# 02_MCU_ANALOG.net
KiCad netlist of a schematic drawn in Altium Designer
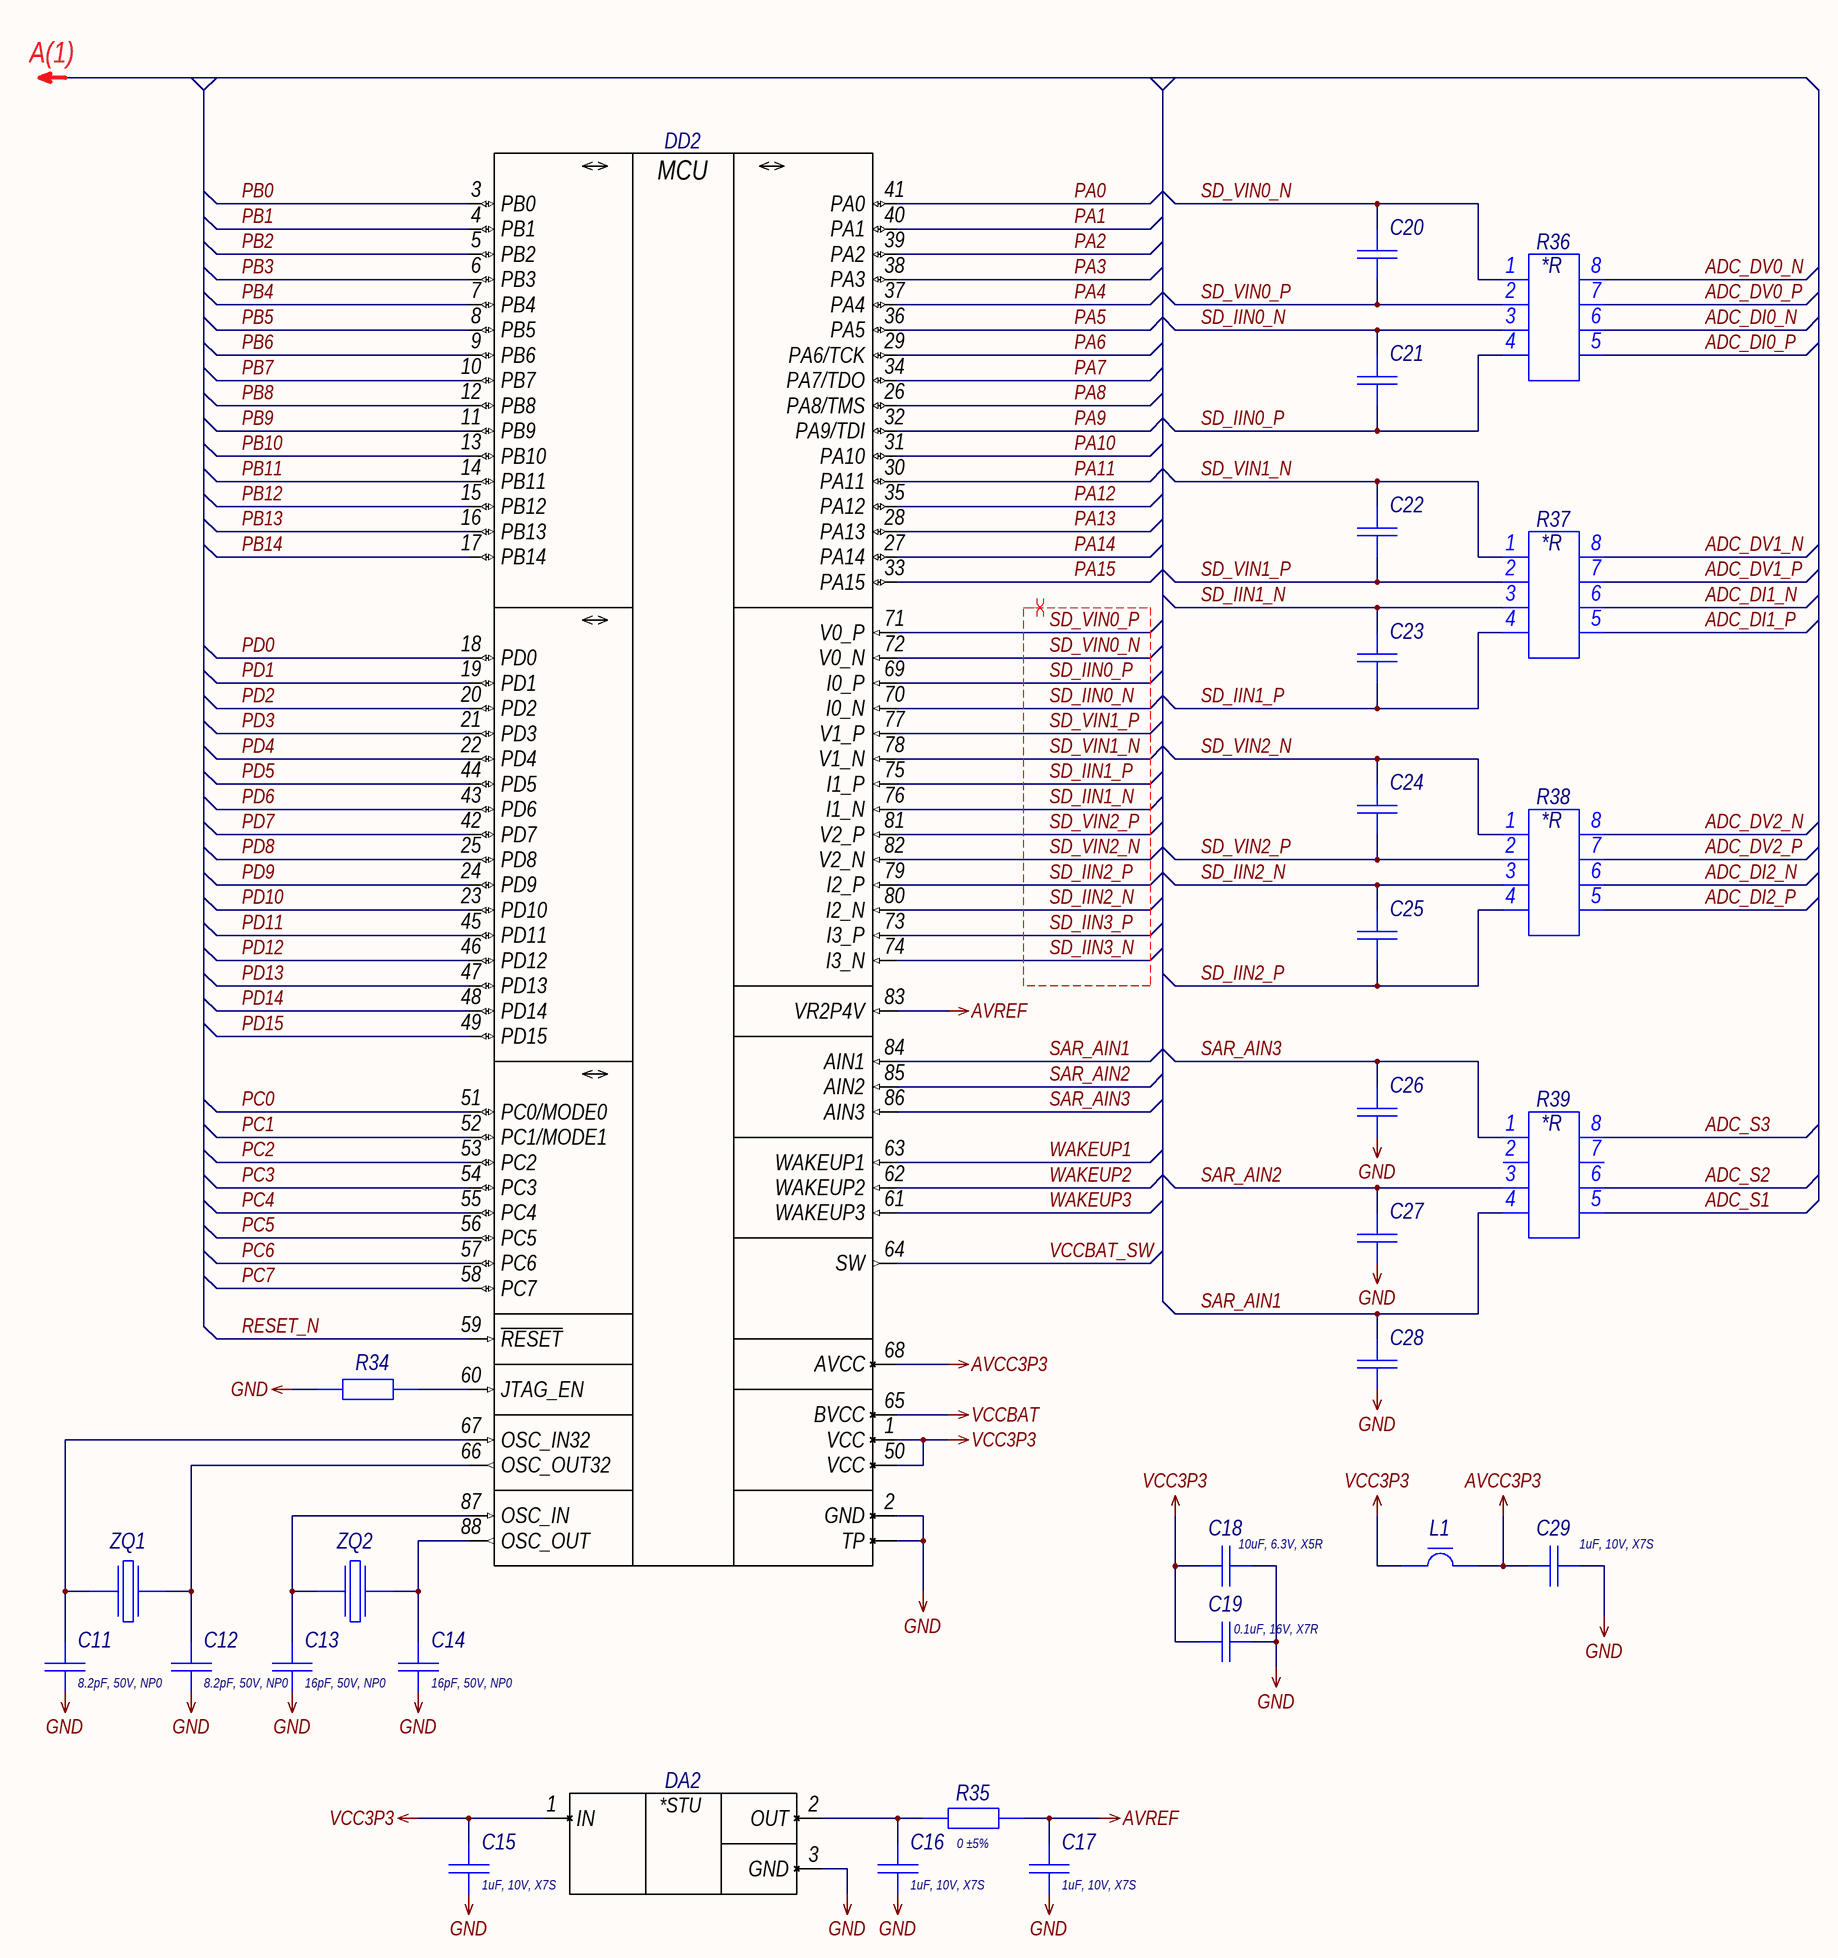
[diagram p0: 02_MCU_ANALOG.SchDoc]

(export (version "E")
  (design (tool "Eeschema 10.0.6"))
  (components
    (comp (ref "C11")
      (value "Capacitor")
      (footprint "C0402_100X050H050_H")
      (fields
        (field (name "SCHEMATIC VALUE") "8.2pF, 50V, NP0")
        (field (name "PART NUMBER") "GCM1555C1H8R2CA16D")
        (field (name "VOLTAGE") "50V")
        (field (name "TOLERANCE") "±0.25pF")
        (field (name "PUBLISHER") "Andrew Danich")
      )
      (libsource (lib "ADLib") (part "Capacitor"))
    )
    (comp (ref "C12")
      (value "Capacitor")
      (footprint "C0402_100X050H050_H")
      (fields
        (field (name "SCHEMATIC VALUE") "8.2pF, 50V, NP0")
        (field (name "PART NUMBER") "GCM1555C1H8R2CA16D")
        (field (name "VOLTAGE") "50V")
        (field (name "TOLERANCE") "±0.25pF")
        (field (name "PUBLISHER") "Andrew Danich")
      )
      (libsource (lib "ADLib") (part "Capacitor"))
    )
    (comp (ref "C13")
      (value "Capacitor")
      (footprint "C0402_100X050H050_H")
      (fields
        (field (name "SCHEMATIC VALUE") "16pF, 50V, NP0")
        (field (name "PART NUMBER") "GRM1555C1H160JA01D")
        (field (name "VOLTAGE") "50V")
        (field (name "TOLERANCE") "±5%")
        (field (name "PUBLISHER") "Andrew Danich")
      )
      (libsource (lib "ADLib") (part "Capacitor"))
    )
    (comp (ref "C14")
      (value "Capacitor")
      (footprint "C0402_100X050H050_H")
      (fields
        (field (name "SCHEMATIC VALUE") "16pF, 50V, NP0")
        (field (name "PART NUMBER") "GRM1555C1H160JA01D")
        (field (name "VOLTAGE") "50V")
        (field (name "TOLERANCE") "±5%")
        (field (name "PUBLISHER") "Andrew Danich")
      )
      (libsource (lib "ADLib") (part "Capacitor"))
    )
    (comp (ref "C15")
      (value "Capacitor")
      (footprint "C0402_100X050H050_H")
      (fields
        (field (name "SCHEMATIC VALUE") "1uF, 10V, X7S")
        (field (name "PART NUMBER") "GRM155C71A105KE11D")
        (field (name "VOLTAGE") "10V")
        (field (name "TOLERANCE") "±10%")
        (field (name "PUBLISHER") "Andrew Danich")
      )
      (libsource (lib "ADLib") (part "Capacitor"))
    )
    (comp (ref "C16")
      (value "Capacitor")
      (footprint "C0402_100X050H050_H")
      (fields
        (field (name "SCHEMATIC VALUE") "1uF, 10V, X7S")
        (field (name "PART NUMBER") "GRM155C71A105KE11D")
        (field (name "VOLTAGE") "10V")
        (field (name "TOLERANCE") "±10%")
        (field (name "PUBLISHER") "Andrew Danich")
      )
      (libsource (lib "ADLib") (part "Capacitor"))
    )
    (comp (ref "C17")
      (value "Capacitor")
      (footprint "C0402_100X050H050_H")
      (fields
        (field (name "SCHEMATIC VALUE") "1uF, 10V, X7S")
        (field (name "PART NUMBER") "GRM155C71A105KE11D")
        (field (name "VOLTAGE") "10V")
        (field (name "TOLERANCE") "±10%")
        (field (name "PUBLISHER") "Andrew Danich")
      )
      (libsource (lib "ADLib") (part "Capacitor"))
    )
    (comp (ref "C18")
      (value "Capacitor")
      (footprint "C0402_100X050H050_H")
      (fields
        (field (name "SCHEMATIC VALUE") "10uF, 6.3V, X5R")
        (field (name "PART NUMBER") "GRM155R60J106ME15D")
        (field (name "VOLTAGE") "6.3V")
        (field (name "TOLERANCE") "±20%")
        (field (name "PUBLISHER") "Andrew Danich")
      )
      (libsource (lib "ADLib") (part "Capacitor"))
    )
    (comp (ref "C19")
      (value "Capacitor")
      (footprint "C0402_100X050H050_H")
      (fields
        (field (name "SCHEMATIC VALUE") "0.1uF, 16V, X7R")
        (field (name "PART NUMBER") "GCM155R71C104KA55D")
        (field (name "VOLTAGE") "16V")
        (field (name "TOLERANCE") "±10%")
        (field (name "PUBLISHER") "Andrew Danich")
      )
      (libsource (lib "ADLib") (part "Capacitor"))
    )
    (comp (ref "C20")
      (value "Capacitor")
      (footprint "C0201_060X030H030_H")
      (fields
        (field (name "PART NUMBER") "GRM033R71A472KA01D")
        (field (name "VOLTAGE") "10V")
        (field (name "TOLERANCE") "±10%")
        (field (name "PUBLISHER") "Andrew Danich")
      )
      (libsource (lib "ADLib") (part "Capacitor"))
    )
    (comp (ref "C21")
      (value "Capacitor")
      (footprint "C0201_060X030H030_H")
      (fields
        (field (name "PART NUMBER") "GRM033R71A472KA01D")
        (field (name "VOLTAGE") "10V")
        (field (name "TOLERANCE") "±10%")
        (field (name "PUBLISHER") "Andrew Danich")
      )
      (libsource (lib "ADLib") (part "Capacitor"))
    )
    (comp (ref "C22")
      (value "Capacitor")
      (footprint "C0201_060X030H030_H")
      (fields
        (field (name "PART NUMBER") "GRM033R71A472KA01D")
        (field (name "VOLTAGE") "10V")
        (field (name "TOLERANCE") "±10%")
        (field (name "PUBLISHER") "Andrew Danich")
      )
      (libsource (lib "ADLib") (part "Capacitor"))
    )
    (comp (ref "C23")
      (value "Capacitor")
      (footprint "C0201_060X030H030_H")
      (fields
        (field (name "PART NUMBER") "GRM033R71A472KA01D")
        (field (name "VOLTAGE") "10V")
        (field (name "TOLERANCE") "±10%")
        (field (name "PUBLISHER") "Andrew Danich")
      )
      (libsource (lib "ADLib") (part "Capacitor"))
    )
    (comp (ref "C24")
      (value "Capacitor")
      (footprint "C0201_060X030H030_H")
      (fields
        (field (name "PART NUMBER") "GRM033R71A472KA01D")
        (field (name "VOLTAGE") "10V")
        (field (name "TOLERANCE") "±10%")
        (field (name "PUBLISHER") "Andrew Danich")
      )
      (libsource (lib "ADLib") (part "Capacitor"))
    )
    (comp (ref "C25")
      (value "Capacitor")
      (footprint "C0201_060X030H030_H")
      (fields
        (field (name "PART NUMBER") "GRM033R71A472KA01D")
        (field (name "VOLTAGE") "10V")
        (field (name "TOLERANCE") "±10%")
        (field (name "PUBLISHER") "Andrew Danich")
      )
      (libsource (lib "ADLib") (part "Capacitor"))
    )
    (comp (ref "C26")
      (value "Capacitor")
      (footprint "C0201_060X030H030_H")
      (fields
        (field (name "PART NUMBER") "GRM033R71A472KA01D")
        (field (name "VOLTAGE") "10V")
        (field (name "TOLERANCE") "±10%")
        (field (name "PUBLISHER") "Andrew Danich")
      )
      (libsource (lib "ADLib") (part "Capacitor"))
    )
    (comp (ref "C27")
      (value "Capacitor")
      (footprint "C0201_060X030H030_H")
      (fields
        (field (name "PART NUMBER") "GRM033R71A472KA01D")
        (field (name "VOLTAGE") "10V")
        (field (name "TOLERANCE") "±10%")
        (field (name "PUBLISHER") "Andrew Danich")
      )
      (libsource (lib "ADLib") (part "Capacitor"))
    )
    (comp (ref "C28")
      (value "Capacitor")
      (footprint "C0201_060X030H030_H")
      (fields
        (field (name "PART NUMBER") "GRM033R71A472KA01D")
        (field (name "VOLTAGE") "10V")
        (field (name "TOLERANCE") "±10%")
        (field (name "PUBLISHER") "Andrew Danich")
      )
      (libsource (lib "ADLib") (part "Capacitor"))
    )
    (comp (ref "C29")
      (value "Capacitor")
      (footprint "C0402_100X050H050_H")
      (fields
        (field (name "SCHEMATIC VALUE") "1uF, 10V, X7S")
        (field (name "PART NUMBER") "GRM155C71A105KE11D")
        (field (name "VOLTAGE") "10V")
        (field (name "TOLERANCE") "±10%")
        (field (name "PUBLISHER") "Andrew Danich")
      )
      (libsource (lib "ADLib") (part "Capacitor"))
    )
    (comp (ref "DA2")
      (value "REF33xxAIDBZx-Series")
      (footprint "SOT-23_190P290X160X145_N")
      (fields
        (field (name "PART NUMBER") "REF3325AIDBZR")
        (field (name "MANUFACTURER") "Texas Instruments")
        (field (name "PUBLISHER") "Andrew Danich")
      )
      (libsource (lib "ADLib") (part "REF33xxAIDBZx-Series"))
    )
    (comp (ref "DD2")
      (value "1986ВК025-Series")
      (footprint "QFN-88_040P1000X1000X080_N")
      (fields
        (field (name "PART NUMBER") "К1986ВК025")
        (field (name "MANUFACTURER") "Миландр")
        (field (name "PUBLISHER") "Andrew Danich")
      )
      (libsource (lib "ADLib_RUS") (part "1986ВК025-Series"))
    )
    (comp (ref "L1")
      (value "FerriteBead")
      (footprint "L0402_100X050H050_H")
      (fields
        (field (name "PART NUMBER") "BLM15HD102SN1D")
        (field (name "TOLERANCE") "±25%")
        (field (name "MANUFACTURER") "Murata")
        (field (name "PUBLISHER") "Andrew Danich")
      )
      (libsource (lib "ADLib") (part "FerriteBead"))
    )
    (comp (ref "R34")
      (value "Resistor")
      (footprint "R0402_100X050H035_H")
      (fields
        (field (name "PART NUMBER") "RC0402JR-070RL")
        (field (name "TOLERANCE") "±5%")
        (field (name "MANUFACTURER") "Yageo")
        (field (name "PUBLISHER") "Andrew Danich")
      )
      (libsource (lib "ADLib") (part "Resistor"))
    )
    (comp (ref "R35")
      (value "Resistor")
      (footprint "R0402_100X050H035_H")
      (fields
        (field (name "PART NUMBER") "RC0402JR-070RL")
        (field (name "TOLERANCE") "±5%")
        (field (name "MANUFACTURER") "Yageo")
        (field (name "SCHEMATIC VALUE") "0 ±5%")
        (field (name "PUBLISHER") "Andrew Danich")
      )
      (libsource (lib "ADLib") (part "Resistor"))
    )
    (comp (ref "R36")
      (value "Resistor-4")
      (footprint "CAY10-x4")
      (fields
        (field (name "PART NUMBER") "CAY10-101J4LF")
        (field (name "TOLERANCE") "±5%")
        (field (name "MANUFACTURER") "Bourns")
        (field (name "PUBLISHER") "Andrew Danich")
      )
      (libsource (lib "ADLib") (part "Resistor-4"))
    )
    (comp (ref "R37")
      (value "Resistor-4")
      (footprint "CAY10-x4")
      (fields
        (field (name "PART NUMBER") "CAY10-101J4LF")
        (field (name "TOLERANCE") "±5%")
        (field (name "MANUFACTURER") "Bourns")
        (field (name "PUBLISHER") "Andrew Danich")
      )
      (libsource (lib "ADLib") (part "Resistor-4"))
    )
    (comp (ref "R38")
      (value "Resistor-4")
      (footprint "CAY10-x4")
      (fields
        (field (name "PART NUMBER") "CAY10-101J4LF")
        (field (name "TOLERANCE") "±5%")
        (field (name "MANUFACTURER") "Bourns")
        (field (name "PUBLISHER") "Andrew Danich")
      )
      (libsource (lib "ADLib") (part "Resistor-4"))
    )
    (comp (ref "R39")
      (value "Resistor-4")
      (footprint "CAY10-x4")
      (fields
        (field (name "PART NUMBER") "CAY10-101J4LF")
        (field (name "TOLERANCE") "±5%")
        (field (name "MANUFACTURER") "Bourns")
        (field (name "PUBLISHER") "Andrew Danich")
      )
      (libsource (lib "ADLib") (part "Resistor-4"))
    )
    (comp (ref "ZQ1")
      (value "Crystal")
      (footprint "SX-3215")
      (fields (field (name "PART NUMBER") "SX-3215 32.768KHz") (field (name "PUBLISHER") "Andrew Danich"))
      (libsource (lib "ADLib") (part "Crystal"))
    )
    (comp (ref "ZQ2")
      (value "Crystal-1_3p")
      (footprint "SMD 3.2x2.5mm")
      (fields
        (field (name "PART NUMBER") "12.88602_KX-7-16.0MHz")
        (field (name "MANUFACTURER") "GEYER ELECTRONIC")
        (field (name "PUBLISHER") "Andrew Danich")
      )
      (libsource (lib "ADLib") (part "Crystal-1_3p"))
    )
  )
  (nets
    (net (code "1") (name "/ADC_DI0_N") (class "Default") (node (ref "R36") (pin "6") (pintype "passive")))
    (net (code "2") (name "/ADC_DI0_P") (class "Default") (node (ref "R36") (pin "5") (pintype "passive")))
    (net (code "3") (name "/ADC_DI1_N") (class "Default") (node (ref "R37") (pin "6") (pintype "passive")))
    (net (code "4") (name "/ADC_DI1_P") (class "Default") (node (ref "R37") (pin "5") (pintype "passive")))
    (net (code "5") (name "/ADC_DI2_N") (class "Default") (node (ref "R38") (pin "6") (pintype "passive")))
    (net (code "6") (name "/ADC_DI2_P") (class "Default") (node (ref "R38") (pin "5") (pintype "passive")))
    (net (code "7") (name "/ADC_DV0_N") (class "Default") (node (ref "R36") (pin "8") (pintype "passive")))
    (net (code "8") (name "/ADC_DV0_P") (class "Default") (node (ref "R36") (pin "7") (pintype "passive")))
    (net (code "9") (name "/ADC_DV1_N") (class "Default") (node (ref "R37") (pin "8") (pintype "passive")))
    (net (code "10") (name "/ADC_DV1_P") (class "Default") (node (ref "R37") (pin "7") (pintype "passive")))
    (net (code "11") (name "/ADC_DV2_N") (class "Default") (node (ref "R38") (pin "8") (pintype "passive")))
    (net (code "12") (name "/ADC_DV2_P") (class "Default") (node (ref "R38") (pin "7") (pintype "passive")))
    (net (code "13") (name "/ADC_S1") (class "Default") (node (ref "R39") (pin "5") (pintype "passive")))
    (net (code "14") (name "/ADC_S2") (class "Default") (node (ref "R39") (pin "6") (pintype "passive")))
    (net (code "15") (name "/ADC_S3") (class "Default") (node (ref "R39") (pin "8") (pintype "passive")))
    (net (code "16") (name "/PA0") (class "Default")
      (node (ref "DD2") (pin "41") (pinfunction "PA0_41") (pintype "bidirectional"))
    )
    (net (code "17") (name "/PA1") (class "Default")
      (node (ref "DD2") (pin "40") (pinfunction "PA1_40") (pintype "bidirectional"))
    )
    (net (code "18") (name "/PA2") (class "Default")
      (node (ref "DD2") (pin "39") (pinfunction "PA2_39") (pintype "bidirectional"))
    )
    (net (code "19") (name "/PA3") (class "Default")
      (node (ref "DD2") (pin "38") (pinfunction "PA3_38") (pintype "bidirectional"))
    )
    (net (code "20") (name "/PA4") (class "Default")
      (node (ref "DD2") (pin "37") (pinfunction "PA4_37") (pintype "bidirectional"))
    )
    (net (code "21") (name "/PA5") (class "Default")
      (node (ref "DD2") (pin "36") (pinfunction "PA5_36") (pintype "bidirectional"))
    )
    (net (code "22") (name "/PA6") (class "Default")
      (node (ref "DD2") (pin "29") (pinfunction "PA6/TCK_29") (pintype "bidirectional"))
    )
    (net (code "23") (name "/PA7") (class "Default")
      (node (ref "DD2") (pin "34") (pinfunction "PA7/TDO_34") (pintype "bidirectional"))
    )
    (net (code "24") (name "/PA8") (class "Default")
      (node (ref "DD2") (pin "26") (pinfunction "PA8/TMS_26") (pintype "bidirectional"))
    )
    (net (code "25") (name "/PA9") (class "Default")
      (node (ref "DD2") (pin "32") (pinfunction "PA9/TDI_32") (pintype "bidirectional"))
    )
    (net (code "26") (name "/PA10") (class "Default")
      (node (ref "DD2") (pin "31") (pinfunction "PA10_31") (pintype "bidirectional"))
    )
    (net (code "27") (name "/PA11") (class "Default")
      (node (ref "DD2") (pin "30") (pinfunction "PA11_30") (pintype "bidirectional"))
    )
    (net (code "28") (name "/PA12") (class "Default")
      (node (ref "DD2") (pin "35") (pinfunction "PA12_35") (pintype "bidirectional"))
    )
    (net (code "29") (name "/PA13") (class "Default")
      (node (ref "DD2") (pin "28") (pinfunction "PA13_28") (pintype "bidirectional"))
    )
    (net (code "30") (name "/PA14") (class "Default")
      (node (ref "DD2") (pin "27") (pinfunction "PA14_27") (pintype "bidirectional"))
    )
    (net (code "31") (name "/PA15") (class "Default")
      (node (ref "DD2") (pin "33") (pinfunction "PA15_33") (pintype "bidirectional"))
    )
    (net (code "32") (name "/PB0") (class "Default")
      (node (ref "DD2") (pin "3") (pinfunction "PB0_3") (pintype "bidirectional"))
    )
    (net (code "33") (name "/PB1") (class "Default")
      (node (ref "DD2") (pin "4") (pinfunction "PB1_4") (pintype "bidirectional"))
    )
    (net (code "34") (name "/PB2") (class "Default")
      (node (ref "DD2") (pin "5") (pinfunction "PB2_5") (pintype "bidirectional"))
    )
    (net (code "35") (name "/PB3") (class "Default")
      (node (ref "DD2") (pin "6") (pinfunction "PB3_6") (pintype "bidirectional"))
    )
    (net (code "36") (name "/PB4") (class "Default")
      (node (ref "DD2") (pin "7") (pinfunction "PB4_7") (pintype "bidirectional"))
    )
    (net (code "37") (name "/PB5") (class "Default")
      (node (ref "DD2") (pin "8") (pinfunction "PB5_8") (pintype "bidirectional"))
    )
    (net (code "38") (name "/PB6") (class "Default")
      (node (ref "DD2") (pin "9") (pinfunction "PB6_9") (pintype "bidirectional"))
    )
    (net (code "39") (name "/PB7") (class "Default")
      (node (ref "DD2") (pin "10") (pinfunction "PB7_10") (pintype "bidirectional"))
    )
    (net (code "40") (name "/PB8") (class "Default")
      (node (ref "DD2") (pin "12") (pinfunction "PB8_12") (pintype "bidirectional"))
    )
    (net (code "41") (name "/PB9") (class "Default")
      (node (ref "DD2") (pin "11") (pinfunction "PB9_11") (pintype "bidirectional"))
    )
    (net (code "42") (name "/PB10") (class "Default")
      (node (ref "DD2") (pin "13") (pinfunction "PB10_13") (pintype "bidirectional"))
    )
    (net (code "43") (name "/PB11") (class "Default")
      (node (ref "DD2") (pin "14") (pinfunction "PB11_14") (pintype "bidirectional"))
    )
    (net (code "44") (name "/PB12") (class "Default")
      (node (ref "DD2") (pin "15") (pinfunction "PB12_15") (pintype "bidirectional"))
    )
    (net (code "45") (name "/PB13") (class "Default")
      (node (ref "DD2") (pin "16") (pinfunction "PB13_16") (pintype "bidirectional"))
    )
    (net (code "46") (name "/PB14") (class "Default")
      (node (ref "DD2") (pin "17") (pinfunction "PB14_17") (pintype "bidirectional"))
    )
    (net (code "47") (name "/PC0") (class "Default")
      (node (ref "DD2") (pin "51") (pinfunction "PC0/MODE0_51") (pintype "bidirectional"))
    )
    (net (code "48") (name "/PC1") (class "Default")
      (node (ref "DD2") (pin "52") (pinfunction "PC1/MODE1_52") (pintype "bidirectional"))
    )
    (net (code "49") (name "/PC2") (class "Default")
      (node (ref "DD2") (pin "53") (pinfunction "PC2_53") (pintype "bidirectional"))
    )
    (net (code "50") (name "/PC3") (class "Default")
      (node (ref "DD2") (pin "54") (pinfunction "PC3_54") (pintype "bidirectional"))
    )
    (net (code "51") (name "/PC4") (class "Default")
      (node (ref "DD2") (pin "55") (pinfunction "PC4_55") (pintype "bidirectional"))
    )
    (net (code "52") (name "/PC5") (class "Default")
      (node (ref "DD2") (pin "56") (pinfunction "PC5_56") (pintype "bidirectional"))
    )
    (net (code "53") (name "/PC6") (class "Default")
      (node (ref "DD2") (pin "57") (pinfunction "PC6_57") (pintype "bidirectional"))
    )
    (net (code "54") (name "/PC7") (class "Default")
      (node (ref "DD2") (pin "58") (pinfunction "PC7_58") (pintype "bidirectional"))
    )
    (net (code "55") (name "/PD0") (class "Default")
      (node (ref "DD2") (pin "18") (pinfunction "PD0_18") (pintype "bidirectional"))
    )
    (net (code "56") (name "/PD1") (class "Default")
      (node (ref "DD2") (pin "19") (pinfunction "PD1_19") (pintype "bidirectional"))
    )
    (net (code "57") (name "/PD2") (class "Default")
      (node (ref "DD2") (pin "20") (pinfunction "PD2_20") (pintype "bidirectional"))
    )
    (net (code "58") (name "/PD3") (class "Default")
      (node (ref "DD2") (pin "21") (pinfunction "PD3_21") (pintype "bidirectional"))
    )
    (net (code "59") (name "/PD4") (class "Default")
      (node (ref "DD2") (pin "22") (pinfunction "PD4_22") (pintype "bidirectional"))
    )
    (net (code "60") (name "/PD5") (class "Default")
      (node (ref "DD2") (pin "44") (pinfunction "PD5_44") (pintype "bidirectional"))
    )
    (net (code "61") (name "/PD6") (class "Default")
      (node (ref "DD2") (pin "43") (pinfunction "PD6_43") (pintype "bidirectional"))
    )
    (net (code "62") (name "/PD7") (class "Default")
      (node (ref "DD2") (pin "42") (pinfunction "PD7_42") (pintype "bidirectional"))
    )
    (net (code "63") (name "/PD8") (class "Default")
      (node (ref "DD2") (pin "25") (pinfunction "PD8_25") (pintype "bidirectional"))
    )
    (net (code "64") (name "/PD9") (class "Default")
      (node (ref "DD2") (pin "24") (pinfunction "PD9_24") (pintype "bidirectional"))
    )
    (net (code "65") (name "/PD10") (class "Default")
      (node (ref "DD2") (pin "23") (pinfunction "PD10_23") (pintype "bidirectional"))
    )
    (net (code "66") (name "/PD11") (class "Default")
      (node (ref "DD2") (pin "45") (pinfunction "PD11_45") (pintype "bidirectional"))
    )
    (net (code "67") (name "/PD12") (class "Default")
      (node (ref "DD2") (pin "46") (pinfunction "PD12_46") (pintype "bidirectional"))
    )
    (net (code "68") (name "/PD13") (class "Default")
      (node (ref "DD2") (pin "47") (pinfunction "PD13_47") (pintype "bidirectional"))
    )
    (net (code "69") (name "/PD14") (class "Default")
      (node (ref "DD2") (pin "48") (pinfunction "PD14_48") (pintype "bidirectional"))
    )
    (net (code "70") (name "/PD15") (class "Default")
      (node (ref "DD2") (pin "49") (pinfunction "PD15_49") (pintype "bidirectional"))
    )
    (net (code "71") (name "/RESET_N") (class "Default")
      (node (ref "DD2") (pin "59") (pinfunction "~{RESET}_59") (pintype "input"))
    )
    (net (code "72") (name "/SAR_AIN1") (class "Default")
      (node (ref "C28") (pin "2") (pinfunction "2_2") (pintype "passive"))
      (node (ref "DD2") (pin "84") (pinfunction "AIN1_84") (pintype "input"))
      (node (ref "R39") (pin "4") (pintype "passive"))
    )
    (net (code "73") (name "/SAR_AIN2") (class "Default")
      (node (ref "C27") (pin "2") (pinfunction "2_2") (pintype "passive"))
      (node (ref "DD2") (pin "85") (pinfunction "AIN2_85") (pintype "input"))
      (node (ref "R39") (pin "3") (pintype "passive"))
    )
    (net (code "74") (name "/SAR_AIN3") (class "Default")
      (node (ref "C26") (pin "2") (pinfunction "2_2") (pintype "passive"))
      (node (ref "DD2") (pin "86") (pinfunction "AIN3_86") (pintype "input"))
      (node (ref "R39") (pin "1") (pintype "passive"))
    )
    (net (code "75") (name "/SD_IIN0_N") (class "Default")
      (node (ref "C21") (pin "2") (pinfunction "2_2") (pintype "passive"))
      (node (ref "DD2") (pin "70") (pinfunction "I0_N_70") (pintype "input"))
      (node (ref "R36") (pin "3") (pintype "passive"))
    )
    (net (code "76") (name "/SD_IIN0_P") (class "Default")
      (node (ref "C21") (pin "1") (pinfunction "1_1") (pintype "passive"))
      (node (ref "DD2") (pin "69") (pinfunction "I0_P_69") (pintype "input"))
      (node (ref "R36") (pin "4") (pintype "passive"))
    )
    (net (code "77") (name "/SD_IIN1_N") (class "Default")
      (node (ref "C23") (pin "2") (pinfunction "2_2") (pintype "passive"))
      (node (ref "DD2") (pin "76") (pinfunction "I1_N_76") (pintype "input"))
      (node (ref "R37") (pin "3") (pintype "passive"))
    )
    (net (code "78") (name "/SD_IIN1_P") (class "Default")
      (node (ref "C23") (pin "1") (pinfunction "1_1") (pintype "passive"))
      (node (ref "DD2") (pin "75") (pinfunction "I1_P_75") (pintype "input"))
      (node (ref "R37") (pin "4") (pintype "passive"))
    )
    (net (code "79") (name "/SD_IIN2_N") (class "Default")
      (node (ref "C25") (pin "2") (pinfunction "2_2") (pintype "passive"))
      (node (ref "DD2") (pin "80") (pinfunction "I2_N_80") (pintype "input"))
      (node (ref "R38") (pin "3") (pintype "passive"))
    )
    (net (code "80") (name "/SD_IIN2_P") (class "Default")
      (node (ref "C25") (pin "1") (pinfunction "1_1") (pintype "passive"))
      (node (ref "DD2") (pin "79") (pinfunction "I2_P_79") (pintype "input"))
      (node (ref "R38") (pin "4") (pintype "passive"))
    )
    (net (code "81") (name "/SD_IIN3_N") (class "Default")
      (node (ref "DD2") (pin "74") (pinfunction "I3_N_74") (pintype "input"))
    )
    (net (code "82") (name "/SD_IIN3_P") (class "Default")
      (node (ref "DD2") (pin "73") (pinfunction "I3_P_73") (pintype "input"))
    )
    (net (code "83") (name "/SD_VIN0_N") (class "Default")
      (node (ref "C20") (pin "2") (pinfunction "2_2") (pintype "passive"))
      (node (ref "DD2") (pin "72") (pinfunction "V0_N_72") (pintype "input"))
      (node (ref "R36") (pin "1") (pintype "passive"))
    )
    (net (code "84") (name "/SD_VIN0_P") (class "Default")
      (node (ref "C20") (pin "1") (pinfunction "1_1") (pintype "passive"))
      (node (ref "DD2") (pin "71") (pinfunction "V0_P_71") (pintype "input"))
      (node (ref "R36") (pin "2") (pintype "passive"))
    )
    (net (code "85") (name "/SD_VIN1_N") (class "Default")
      (node (ref "C22") (pin "2") (pinfunction "2_2") (pintype "passive"))
      (node (ref "DD2") (pin "78") (pinfunction "V1_N_78") (pintype "input"))
      (node (ref "R37") (pin "1") (pintype "passive"))
    )
    (net (code "86") (name "/SD_VIN1_P") (class "Default")
      (node (ref "C22") (pin "1") (pinfunction "1_1") (pintype "passive"))
      (node (ref "DD2") (pin "77") (pinfunction "V1_P_77") (pintype "input"))
      (node (ref "R37") (pin "2") (pintype "passive"))
    )
    (net (code "87") (name "/SD_VIN2_N") (class "Default")
      (node (ref "C24") (pin "2") (pinfunction "2_2") (pintype "passive"))
      (node (ref "DD2") (pin "82") (pinfunction "V2_N_82") (pintype "input"))
      (node (ref "R38") (pin "1") (pintype "passive"))
    )
    (net (code "88") (name "/SD_VIN2_P") (class "Default")
      (node (ref "C24") (pin "1") (pinfunction "1_1") (pintype "passive"))
      (node (ref "DD2") (pin "81") (pinfunction "V2_P_81") (pintype "input"))
      (node (ref "R38") (pin "2") (pintype "passive"))
    )
    (net (code "89") (name "/VCCBAT_SW") (class "Default")
      (node (ref "DD2") (pin "64") (pinfunction "SW_64") (pintype "output"))
    )
    (net (code "90") (name "/WAKEUP1") (class "Default")
      (node (ref "DD2") (pin "63") (pinfunction "WAKEUP1_63") (pintype "input"))
    )
    (net (code "91") (name "/WAKEUP2") (class "Default")
      (node (ref "DD2") (pin "62") (pinfunction "WAKEUP2_62") (pintype "input"))
    )
    (net (code "92") (name "/WAKEUP3") (class "Default")
      (node (ref "DD2") (pin "61") (pinfunction "WAKEUP3_61") (pintype "input"))
    )
    (net (code "93") (name "AVCC3P3") (class "Default")
      (node (ref "C29") (pin "2") (pinfunction "2_2") (pintype "passive"))
      (node (ref "DD2") (pin "68") (pinfunction "AVCC_68") (pintype "power_in"))
      (node (ref "L1") (pin "2") (pinfunction "2_2") (pintype "passive"))
    )
    (net (code "94") (name "AVREF") (class "Default")
      (node (ref "C17") (pin "2") (pinfunction "2_2") (pintype "passive"))
      (node (ref "DD2") (pin "83") (pinfunction "VR2P4V_83") (pintype "input"))
      (node (ref "R35") (pin "1") (pinfunction "1_1") (pintype "passive"))
    )
    (net (code "95") (name "GND") (class "Default")
      (node (ref "C11") (pin "1") (pinfunction "1_1") (pintype "passive"))
      (node (ref "C12") (pin "1") (pinfunction "1_1") (pintype "passive"))
      (node (ref "C13") (pin "1") (pinfunction "1_1") (pintype "passive"))
      (node (ref "C14") (pin "1") (pinfunction "1_1") (pintype "passive"))
      (node (ref "C15") (pin "1") (pinfunction "1_1") (pintype "passive"))
      (node (ref "C16") (pin "1") (pinfunction "1_1") (pintype "passive"))
      (node (ref "C17") (pin "1") (pinfunction "1_1") (pintype "passive"))
      (node (ref "C18") (pin "1") (pinfunction "1_1") (pintype "passive"))
      (node (ref "C19") (pin "2") (pinfunction "2_2") (pintype "passive"))
      (node (ref "C26") (pin "1") (pinfunction "1_1") (pintype "passive"))
      (node (ref "C27") (pin "1") (pinfunction "1_1") (pintype "passive"))
      (node (ref "C28") (pin "1") (pinfunction "1_1") (pintype "passive"))
      (node (ref "C29") (pin "1") (pinfunction "1_1") (pintype "passive"))
      (node (ref "DA2") (pin "3") (pinfunction "GND_3") (pintype "power_in"))
      (node (ref "DD2") (pin "2") (pinfunction "GND_2") (pintype "power_in"))
      (node (ref "DD2") (pin "TP") (pinfunction "TP_TP") (pintype "power_in"))
      (node (ref "R34") (pin "2") (pinfunction "2_2") (pintype "passive"))
    )
    (net (code "96") (name "Net-(DA2-OUT)") (class "Default")
      (node (ref "C16") (pin "2") (pinfunction "2_2") (pintype "passive"))
      (node (ref "DA2") (pin "2") (pinfunction "OUT_2") (pintype "power_in"))
      (node (ref "R35") (pin "2") (pinfunction "2_2") (pintype "passive"))
    )
    (net (code "97") (name "Net-(DD2-JTAG_EN)") (class "Default")
      (node (ref "DD2") (pin "60") (pinfunction "JTAG_EN_60") (pintype "input"))
      (node (ref "R34") (pin "1") (pinfunction "1_1") (pintype "passive"))
    )
    (net (code "98") (name "Net-(DD2-OSC_IN)") (class "Default")
      (node (ref "C13") (pin "2") (pinfunction "2_2") (pintype "passive"))
      (node (ref "DD2") (pin "87") (pinfunction "OSC_IN_87") (pintype "input"))
      (node (ref "ZQ2") (pin "1") (pinfunction "1_1") (pintype "passive"))
    )
    (net (code "99") (name "Net-(DD2-OSC_IN32)") (class "Default")
      (node (ref "C11") (pin "2") (pinfunction "2_2") (pintype "passive"))
      (node (ref "DD2") (pin "67") (pinfunction "OSC_IN32_67") (pintype "input"))
      (node (ref "ZQ1") (pin "1") (pinfunction "1_1") (pintype "passive"))
    )
    (net (code "100") (name "Net-(DD2-OSC_OUT)") (class "Default")
      (node (ref "C14") (pin "2") (pinfunction "2_2") (pintype "passive"))
      (node (ref "DD2") (pin "88") (pinfunction "OSC_OUT_88") (pintype "output"))
      (node (ref "ZQ2") (pin "3") (pinfunction "3_3") (pintype "passive"))
    )
    (net (code "101") (name "Net-(DD2-OSC_OUT32)") (class "Default")
      (node (ref "C12") (pin "2") (pinfunction "2_2") (pintype "passive"))
      (node (ref "DD2") (pin "66") (pinfunction "OSC_OUT32_66") (pintype "output"))
      (node (ref "ZQ1") (pin "3") (pinfunction "3_3") (pintype "passive"))
    )
    (net (code "102") (name "VCC3P3") (class "Default")
      (node (ref "C15") (pin "2") (pinfunction "2_2") (pintype "passive"))
      (node (ref "C18") (pin "2") (pinfunction "2_2") (pintype "passive"))
      (node (ref "C19") (pin "1") (pinfunction "1_1") (pintype "passive"))
      (node (ref "DA2") (pin "1") (pinfunction "IN_1") (pintype "power_in"))
      (node (ref "DD2") (pin "1") (pinfunction "VCC_1") (pintype "power_in"))
      (node (ref "DD2") (pin "50") (pinfunction "VCC_50") (pintype "power_in"))
      (node (ref "L1") (pin "1") (pinfunction "1_1") (pintype "passive"))
    )
    (net (code "103") (name "VCCBAT") (class "Default")
      (node (ref "DD2") (pin "65") (pinfunction "BVCC_65") (pintype "power_in"))
    )
    (net (code "104") (name "unconnected-(R39-Pad2)") (class "Default")
      (node (ref "R39") (pin "2") (pintype "passive"))
    )
    (net (code "105") (name "unconnected-(R39-Pad7)") (class "Default")
      (node (ref "R39") (pin "7") (pintype "passive"))
    )
  )
)
